# Adafruit_NeoPixel_Ring_12_rev_B.net
KiCad netlist of a schematic drawn in EAGLE
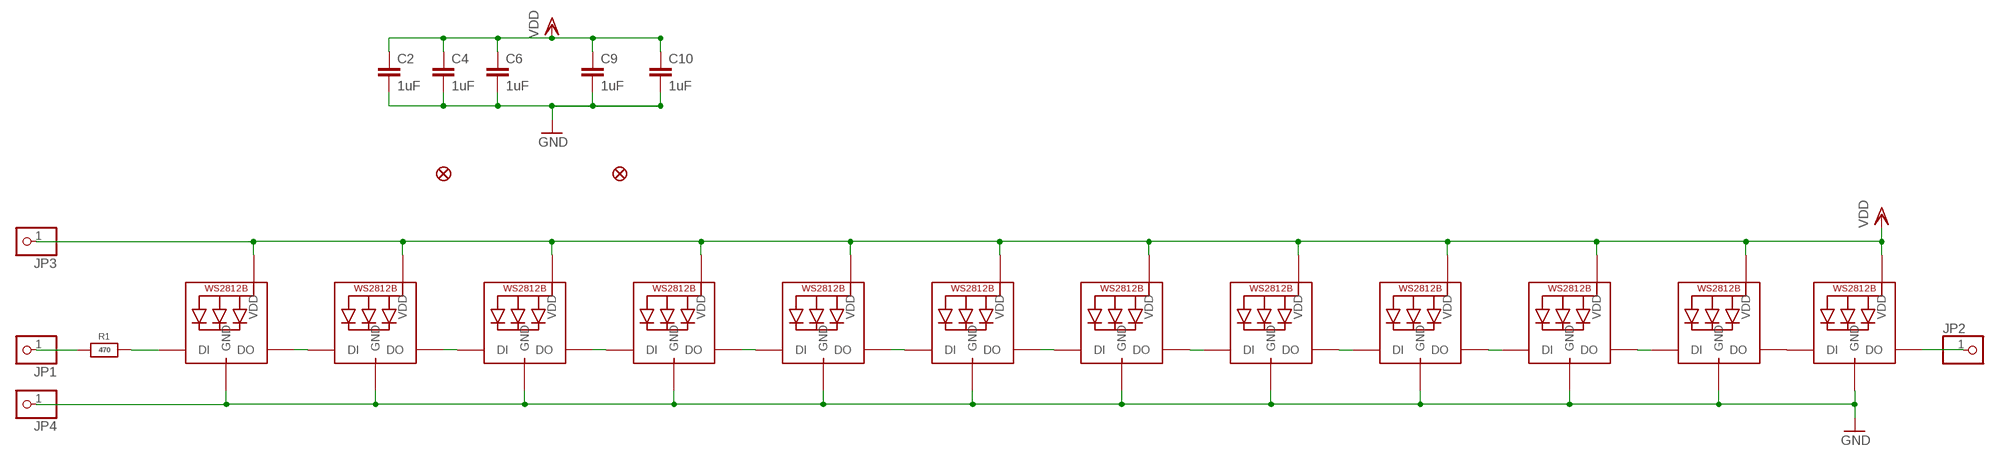
[diagram p0: schematic, sheet 1]

(export (version "E")
  (design (tool "Eeschema 10.0.6"))
  (components
    (comp (ref "C2")
      (value "1uF")
      (footprint "eagle-import:C0603")
      (libsource (lib "eagle-import") (part "C-EUC0603"))
    )
    (comp (ref "C4")
      (value "1uF")
      (footprint "eagle-import:C0603")
      (libsource (lib "eagle-import") (part "C-EUC0603"))
    )
    (comp (ref "C6")
      (value "1uF")
      (footprint "eagle-import:C0603")
      (libsource (lib "eagle-import") (part "C-EUC0603"))
    )
    (comp (ref "C9")
      (value "1uF")
      (footprint "eagle-import:C0603")
      (libsource (lib "eagle-import") (part "C-EUC0603"))
    )
    (comp (ref "C10")
      (value "1uF")
      (footprint "eagle-import:C0603")
      (libsource (lib "eagle-import") (part "C-EUC0603"))
    )
    (comp (ref "FID1")
      (value "FIDUCIAL_1MM")
      (footprint "eagle-import:FIDUCIAL_1MM")
      (libsource (lib "eagle-import") (part "FIDUCIAL_1MM"))
    )
    (comp (ref "FID2")
      (value "FIDUCIAL_1MM")
      (footprint "eagle-import:FIDUCIAL_1MM")
      (libsource (lib "eagle-import") (part "FIDUCIAL_1MM"))
    )
    (comp (ref "JP1")
      (value "PINHD-1X1CB")
      (footprint "eagle-import:1X01-CLEANBIG")
      (libsource (lib "eagle-import") (part "PINHD-1X1CB"))
    )
    (comp (ref "JP2")
      (value "PINHD-1X1CB")
      (footprint "eagle-import:1X01-CLEANBIG")
      (libsource (lib "eagle-import") (part "PINHD-1X1CB"))
    )
    (comp (ref "JP3")
      (value "PINHD-1X1CB")
      (footprint "eagle-import:1X01-CLEANBIG")
      (libsource (lib "eagle-import") (part "PINHD-1X1CB"))
    )
    (comp (ref "JP4")
      (value "PINHD-1X1CB")
      (footprint "eagle-import:1X01-CLEANBIG")
      (libsource (lib "eagle-import") (part "PINHD-1X1CB"))
    )
    (comp (ref "LED1")
      (value "WS2812B_5050N")
      (footprint "eagle-import:WS2812B-NARROW")
      (libsource (lib "eagle-import") (part "WS2812B_5050N"))
    )
    (comp (ref "LED2")
      (value "WS2812B_5050N")
      (footprint "eagle-import:WS2812B-NARROW")
      (libsource (lib "eagle-import") (part "WS2812B_5050N"))
    )
    (comp (ref "LED3")
      (value "WS2812B_5050N")
      (footprint "eagle-import:WS2812B-NARROW")
      (libsource (lib "eagle-import") (part "WS2812B_5050N"))
    )
    (comp (ref "LED4")
      (value "WS2812B_5050N")
      (footprint "eagle-import:WS2812B-NARROW")
      (libsource (lib "eagle-import") (part "WS2812B_5050N"))
    )
    (comp (ref "LED5")
      (value "WS2812B_5050N")
      (footprint "eagle-import:WS2812B-NARROW")
      (libsource (lib "eagle-import") (part "WS2812B_5050N"))
    )
    (comp (ref "LED6")
      (value "WS2812B_5050N")
      (footprint "eagle-import:WS2812B-NARROW")
      (libsource (lib "eagle-import") (part "WS2812B_5050N"))
    )
    (comp (ref "LED7")
      (value "WS2812B_5050N")
      (footprint "eagle-import:WS2812B-NARROW")
      (libsource (lib "eagle-import") (part "WS2812B_5050N"))
    )
    (comp (ref "LED8")
      (value "WS2812B_5050N")
      (footprint "eagle-import:WS2812B-NARROW")
      (libsource (lib "eagle-import") (part "WS2812B_5050N"))
    )
    (comp (ref "LED9")
      (value "WS2812B_5050N")
      (footprint "eagle-import:WS2812B-NARROW")
      (libsource (lib "eagle-import") (part "WS2812B_5050N"))
    )
    (comp (ref "LED10")
      (value "WS2812B_5050N")
      (footprint "eagle-import:WS2812B-NARROW")
      (libsource (lib "eagle-import") (part "WS2812B_5050N"))
    )
    (comp (ref "LED11")
      (value "WS2812B_5050N")
      (footprint "eagle-import:WS2812B-NARROW")
      (libsource (lib "eagle-import") (part "WS2812B_5050N"))
    )
    (comp (ref "LED12")
      (value "WS2812B_5050N")
      (footprint "eagle-import:WS2812B-NARROW")
      (libsource (lib "eagle-import") (part "WS2812B_5050N"))
    )
    (comp (ref "R1")
      (value "470")
      (footprint "eagle-import:0603-NO")
      (libsource (lib "eagle-import") (part "RESISTOR_0603_NOOUT"))
    )
  )
  (nets
    (net (code "1") (name "GND") (class "Default")
      (node (ref "C10") (pin "2") (pinfunction "2_2") (pintype "passive"))
      (node (ref "C2") (pin "2") (pinfunction "2_2") (pintype "passive"))
      (node (ref "C4") (pin "2") (pinfunction "2_2") (pintype "passive"))
      (node (ref "C6") (pin "2") (pinfunction "2_2") (pintype "passive"))
      (node (ref "C9") (pin "2") (pinfunction "2_2") (pintype "passive"))
      (node (ref "JP4") (pin "1") (pinfunction "1_1") (pintype "passive"))
      (node (ref "LED1") (pin "3-GND") (pinfunction "GND_3-GND") (pintype "power_in"))
      (node (ref "LED10") (pin "3-GND") (pinfunction "GND_3-GND") (pintype "power_in"))
      (node (ref "LED11") (pin "3-GND") (pinfunction "GND_3-GND") (pintype "power_in"))
      (node (ref "LED12") (pin "3-GND") (pinfunction "GND_3-GND") (pintype "power_in"))
      (node (ref "LED2") (pin "3-GND") (pinfunction "GND_3-GND") (pintype "power_in"))
      (node (ref "LED3") (pin "3-GND") (pinfunction "GND_3-GND") (pintype "power_in"))
      (node (ref "LED4") (pin "3-GND") (pinfunction "GND_3-GND") (pintype "power_in"))
      (node (ref "LED5") (pin "3-GND") (pinfunction "GND_3-GND") (pintype "power_in"))
      (node (ref "LED6") (pin "3-GND") (pinfunction "GND_3-GND") (pintype "power_in"))
      (node (ref "LED7") (pin "3-GND") (pinfunction "GND_3-GND") (pintype "power_in"))
      (node (ref "LED8") (pin "3-GND") (pinfunction "GND_3-GND") (pintype "power_in"))
      (node (ref "LED9") (pin "3-GND") (pinfunction "GND_3-GND") (pintype "power_in"))
    )
    (net (code "2") (name "Net-(JP1-Pad1)") (class "Default")
      (node (ref "JP1") (pin "1") (pinfunction "1_1") (pintype "passive"))
      (node (ref "R1") (pin "1") (pinfunction "1_1") (pintype "passive"))
    )
    (net (code "3") (name "Net-(LED1-DI)") (class "Default")
      (node (ref "LED1") (pin "4-DIN") (pinfunction "DI_4-DIN") (pintype "input"))
      (node (ref "R1") (pin "2") (pinfunction "2_2") (pintype "passive"))
    )
    (net (code "4") (name "Net-(LED1-DO)") (class "Default")
      (node (ref "LED1") (pin "2-DOUT") (pinfunction "DO_2-DOUT") (pintype "output"))
      (node (ref "LED2") (pin "4-DIN") (pinfunction "DI_4-DIN") (pintype "input"))
    )
    (net (code "5") (name "Net-(LED2-DO)") (class "Default")
      (node (ref "LED2") (pin "2-DOUT") (pinfunction "DO_2-DOUT") (pintype "output"))
      (node (ref "LED3") (pin "4-DIN") (pinfunction "DI_4-DIN") (pintype "input"))
    )
    (net (code "6") (name "Net-(LED3-DO)") (class "Default")
      (node (ref "LED3") (pin "2-DOUT") (pinfunction "DO_2-DOUT") (pintype "output"))
      (node (ref "LED4") (pin "4-DIN") (pinfunction "DI_4-DIN") (pintype "input"))
    )
    (net (code "7") (name "Net-(LED4-DO)") (class "Default")
      (node (ref "LED4") (pin "2-DOUT") (pinfunction "DO_2-DOUT") (pintype "output"))
      (node (ref "LED5") (pin "4-DIN") (pinfunction "DI_4-DIN") (pintype "input"))
    )
    (net (code "8") (name "Net-(LED5-DO)") (class "Default")
      (node (ref "LED5") (pin "2-DOUT") (pinfunction "DO_2-DOUT") (pintype "output"))
      (node (ref "LED6") (pin "4-DIN") (pinfunction "DI_4-DIN") (pintype "input"))
    )
    (net (code "9") (name "Net-(LED6-DO)") (class "Default")
      (node (ref "LED6") (pin "2-DOUT") (pinfunction "DO_2-DOUT") (pintype "output"))
      (node (ref "LED7") (pin "4-DIN") (pinfunction "DI_4-DIN") (pintype "input"))
    )
    (net (code "10") (name "Net-(LED7-DO)") (class "Default")
      (node (ref "LED7") (pin "2-DOUT") (pinfunction "DO_2-DOUT") (pintype "output"))
      (node (ref "LED8") (pin "4-DIN") (pinfunction "DI_4-DIN") (pintype "input"))
    )
    (net (code "11") (name "Net-(LED8-DO)") (class "Default")
      (node (ref "LED8") (pin "2-DOUT") (pinfunction "DO_2-DOUT") (pintype "output"))
      (node (ref "LED9") (pin "4-DIN") (pinfunction "DI_4-DIN") (pintype "input"))
    )
    (net (code "12") (name "Net-(LED10-DI)") (class "Default")
      (node (ref "LED10") (pin "4-DIN") (pinfunction "DI_4-DIN") (pintype "input"))
      (node (ref "LED9") (pin "2-DOUT") (pinfunction "DO_2-DOUT") (pintype "output"))
    )
    (net (code "13") (name "Net-(LED10-DO)") (class "Default")
      (node (ref "LED10") (pin "2-DOUT") (pinfunction "DO_2-DOUT") (pintype "output"))
      (node (ref "LED11") (pin "4-DIN") (pinfunction "DI_4-DIN") (pintype "input"))
    )
    (net (code "14") (name "Net-(LED11-DO)") (class "Default")
      (node (ref "LED11") (pin "2-DOUT") (pinfunction "DO_2-DOUT") (pintype "output"))
      (node (ref "LED12") (pin "4-DIN") (pinfunction "DI_4-DIN") (pintype "input"))
    )
    (net (code "15") (name "Net-(LED12-DO)") (class "Default")
      (node (ref "JP2") (pin "1") (pinfunction "1_1") (pintype "passive"))
      (node (ref "LED12") (pin "2-DOUT") (pinfunction "DO_2-DOUT") (pintype "output"))
    )
    (net (code "16") (name "VDD") (class "Default")
      (node (ref "C10") (pin "1") (pinfunction "1_1") (pintype "passive"))
      (node (ref "C2") (pin "1") (pinfunction "1_1") (pintype "passive"))
      (node (ref "C4") (pin "1") (pinfunction "1_1") (pintype "passive"))
      (node (ref "C6") (pin "1") (pinfunction "1_1") (pintype "passive"))
      (node (ref "C9") (pin "1") (pinfunction "1_1") (pintype "passive"))
      (node (ref "JP3") (pin "1") (pinfunction "1_1") (pintype "passive"))
      (node (ref "LED1") (pin "1-VDD") (pinfunction "VDD_1-VDD") (pintype "power_in"))
      (node (ref "LED10") (pin "1-VDD") (pinfunction "VDD_1-VDD") (pintype "power_in"))
      (node (ref "LED11") (pin "1-VDD") (pinfunction "VDD_1-VDD") (pintype "power_in"))
      (node (ref "LED12") (pin "1-VDD") (pinfunction "VDD_1-VDD") (pintype "power_in"))
      (node (ref "LED2") (pin "1-VDD") (pinfunction "VDD_1-VDD") (pintype "power_in"))
      (node (ref "LED3") (pin "1-VDD") (pinfunction "VDD_1-VDD") (pintype "power_in"))
      (node (ref "LED4") (pin "1-VDD") (pinfunction "VDD_1-VDD") (pintype "power_in"))
      (node (ref "LED5") (pin "1-VDD") (pinfunction "VDD_1-VDD") (pintype "power_in"))
      (node (ref "LED6") (pin "1-VDD") (pinfunction "VDD_1-VDD") (pintype "power_in"))
      (node (ref "LED7") (pin "1-VDD") (pinfunction "VDD_1-VDD") (pintype "power_in"))
      (node (ref "LED8") (pin "1-VDD") (pinfunction "VDD_1-VDD") (pintype "power_in"))
      (node (ref "LED9") (pin "1-VDD") (pinfunction "VDD_1-VDD") (pintype "power_in"))
    )
  )
)
